# Freedom_Proto_v2.net
KiCad netlist of a schematic drawn in EAGLE
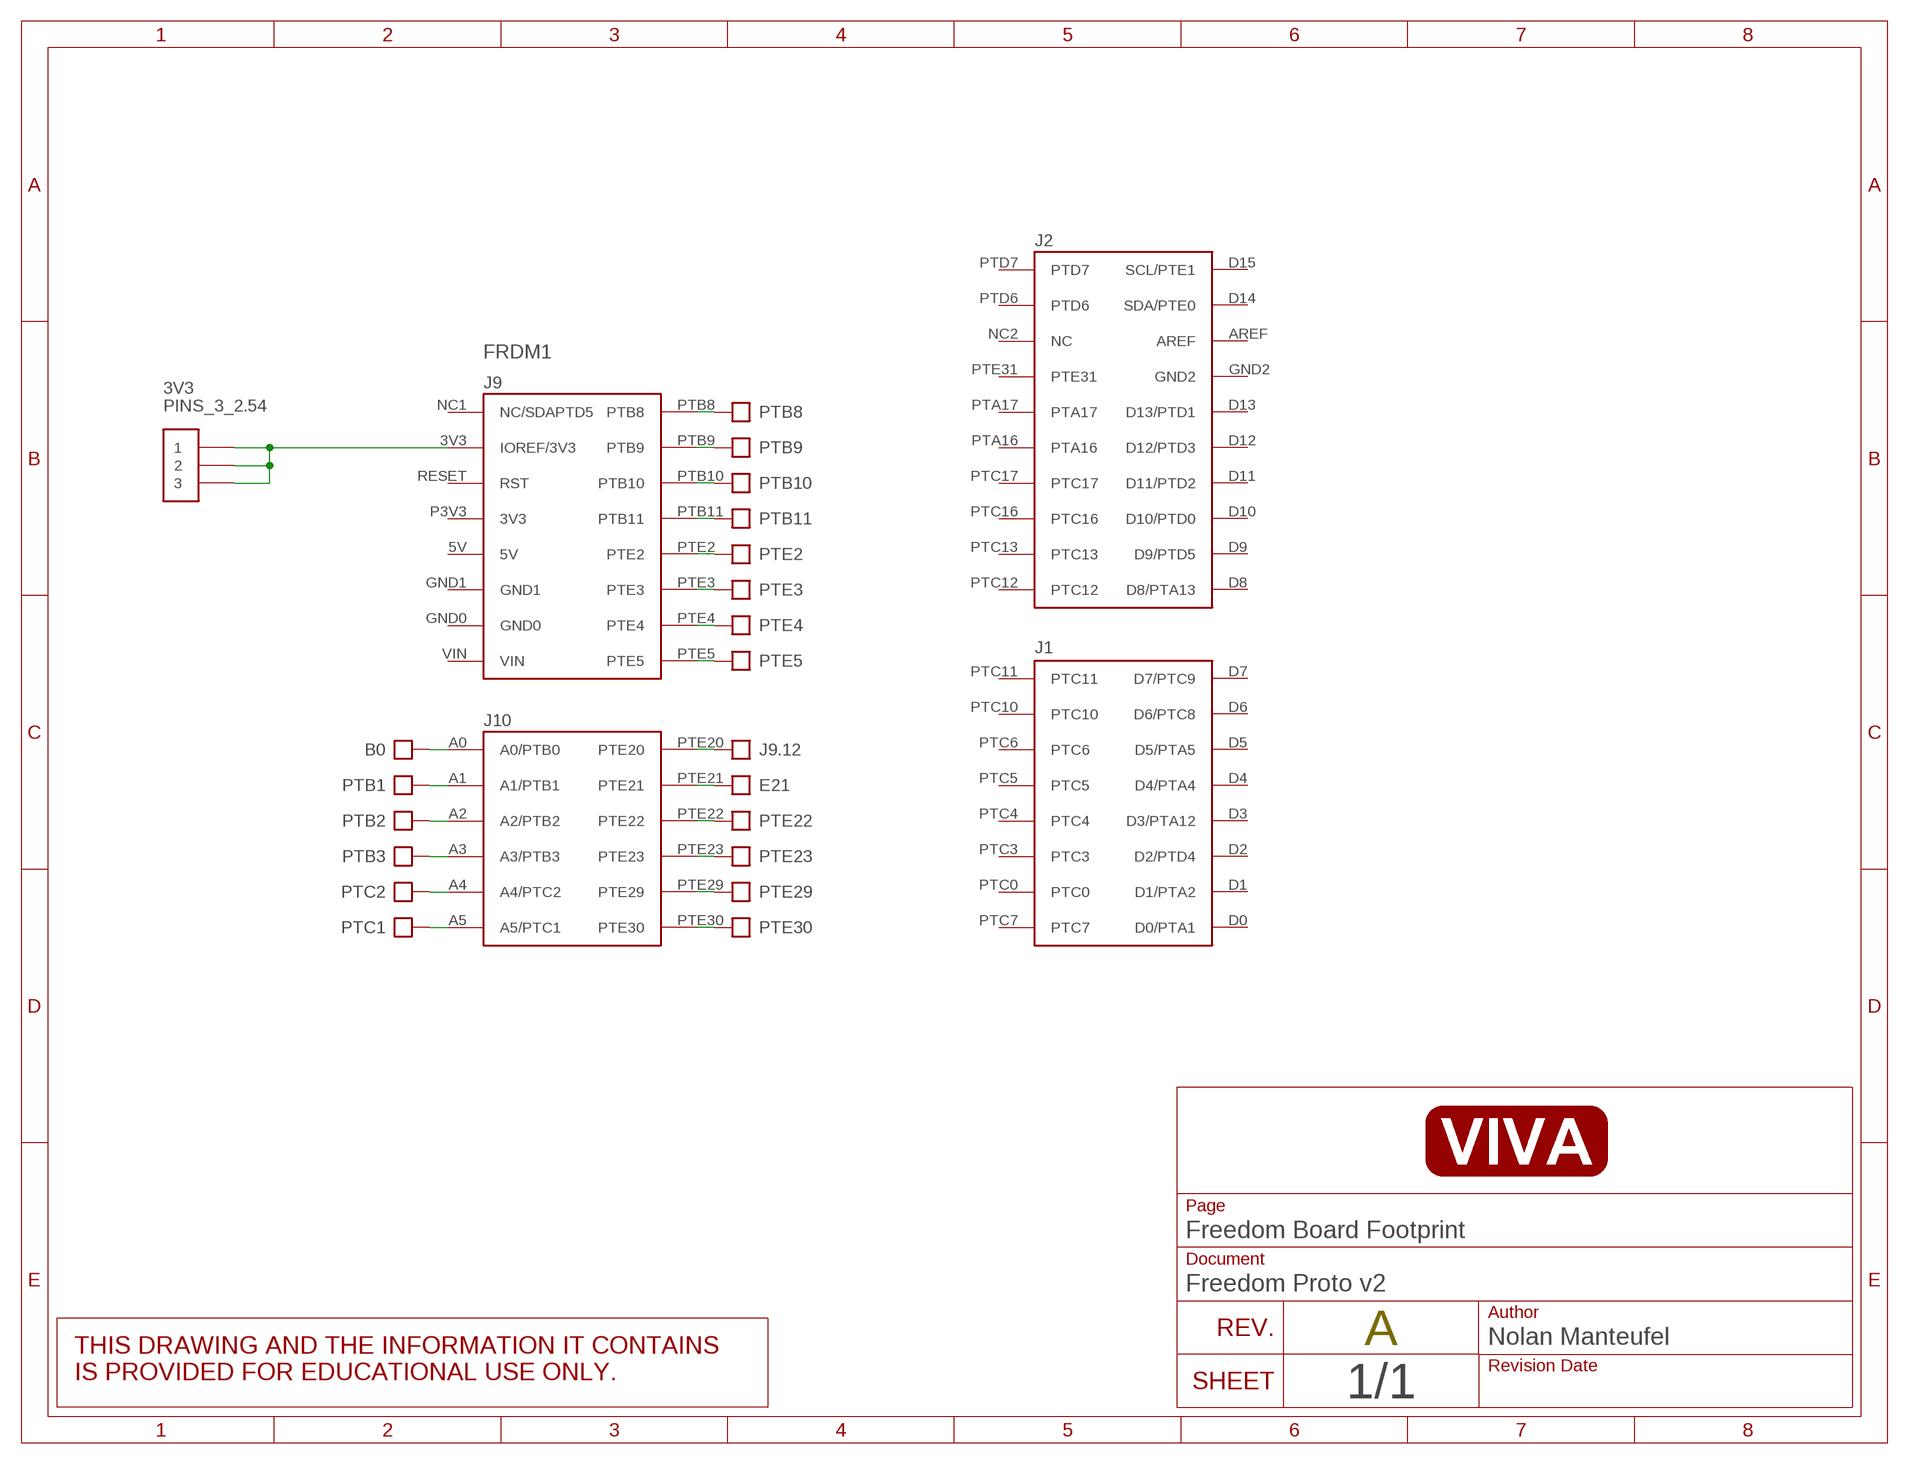
[diagram p0: schematic, sheet 1]

(export (version "E")
  (design (tool "Eeschema 10.0.6"))
  (components
    (comp (ref "3V3")
      (value "PINS_3_2.54")
      (footprint "eagle-import:PINS_3")
      (libsource (lib "eagle-import") (part "PINS_3_2.54"))
    )
    (comp (ref "B0")
      (value "PINS_1")
      (footprint "eagle-import:PINS_1_TEXT")
      (libsource (lib "eagle-import") (part "PINS_1"))
    )
    (comp (ref "E21")
      (value "PINS_1")
      (footprint "eagle-import:PINS_1_TEXT")
      (libsource (lib "eagle-import") (part "PINS_1"))
    )
    (comp (ref "FRDM1")
      (value "FRDM-KL25ZNORMAL")
      (footprint "eagle-import:FRDM_KL25Z_NORMAL")
      (libsource (lib "eagle-import") (part "FRDM-KL25ZNORMAL"))
    )
    (comp (ref "J9.12")
      (value "PINS_1")
      (footprint "eagle-import:PINS_1_TEXT")
      (libsource (lib "eagle-import") (part "PINS_1"))
    )
    (comp (ref "PTB1")
      (value "PINS_1")
      (footprint "eagle-import:PINS_1_TEXT")
      (libsource (lib "eagle-import") (part "PINS_1"))
    )
    (comp (ref "PTB2")
      (value "PINS_1")
      (footprint "eagle-import:PINS_1_TEXT")
      (libsource (lib "eagle-import") (part "PINS_1"))
    )
    (comp (ref "PTB3")
      (value "PINS_1")
      (footprint "eagle-import:PINS_1_TEXT")
      (libsource (lib "eagle-import") (part "PINS_1"))
    )
    (comp (ref "PTB8")
      (value "PINS_1")
      (footprint "eagle-import:PINS_1_TEXT")
      (libsource (lib "eagle-import") (part "PINS_1"))
    )
    (comp (ref "PTB9")
      (value "PINS_1")
      (footprint "eagle-import:PINS_1_TEXT")
      (libsource (lib "eagle-import") (part "PINS_1"))
    )
    (comp (ref "PTB10")
      (value "PINS_1")
      (footprint "eagle-import:PINS_1_TEXT")
      (libsource (lib "eagle-import") (part "PINS_1"))
    )
    (comp (ref "PTB11")
      (value "PINS_1")
      (footprint "eagle-import:PINS_1_TEXT")
      (libsource (lib "eagle-import") (part "PINS_1"))
    )
    (comp (ref "PTC1")
      (value "PINS_1")
      (footprint "eagle-import:PINS_1_TEXT")
      (libsource (lib "eagle-import") (part "PINS_1"))
    )
    (comp (ref "PTC2")
      (value "PINS_1")
      (footprint "eagle-import:PINS_1_TEXT")
      (libsource (lib "eagle-import") (part "PINS_1"))
    )
    (comp (ref "PTE2")
      (value "PINS_1")
      (footprint "eagle-import:PINS_1_TEXT")
      (libsource (lib "eagle-import") (part "PINS_1"))
    )
    (comp (ref "PTE3")
      (value "PINS_1")
      (footprint "eagle-import:PINS_1_TEXT")
      (libsource (lib "eagle-import") (part "PINS_1"))
    )
    (comp (ref "PTE4")
      (value "PINS_1")
      (footprint "eagle-import:PINS_1_TEXT")
      (libsource (lib "eagle-import") (part "PINS_1"))
    )
    (comp (ref "PTE5")
      (value "PINS_1")
      (footprint "eagle-import:PINS_1_TEXT")
      (libsource (lib "eagle-import") (part "PINS_1"))
    )
    (comp (ref "PTE22")
      (value "PINS_1")
      (footprint "eagle-import:PINS_1_TEXT")
      (libsource (lib "eagle-import") (part "PINS_1"))
    )
    (comp (ref "PTE23")
      (value "PINS_1")
      (footprint "eagle-import:PINS_1_TEXT")
      (libsource (lib "eagle-import") (part "PINS_1"))
    )
    (comp (ref "PTE29")
      (value "PINS_1")
      (footprint "eagle-import:PINS_1_TEXT")
      (libsource (lib "eagle-import") (part "PINS_1"))
    )
    (comp (ref "PTE30")
      (value "PINS_1")
      (footprint "eagle-import:PINS_1_TEXT")
      (libsource (lib "eagle-import") (part "PINS_1"))
    )
  )
  (nets
    (net (code "1") (name "Net-(E21-Pad1)") (class "Default")
      (node (ref "E21") (pin "1") (pinfunction "1_1") (pintype "bidirectional"))
      (node (ref "FRDM1") (pin "PTE21") (pinfunction "PTE21_PTE21") (pintype "bidirectional"))
    )
    (net (code "2") (name "Net-(FRDM1-A0{slash}PTB0)") (class "Default")
      (node (ref "B0") (pin "1") (pinfunction "1_1") (pintype "bidirectional"))
      (node (ref "FRDM1") (pin "A0") (pinfunction "A0/PTB0_A0") (pintype "bidirectional"))
    )
    (net (code "3") (name "Net-(FRDM1-A1{slash}PTB1)") (class "Default")
      (node (ref "FRDM1") (pin "A1") (pinfunction "A1/PTB1_A1") (pintype "bidirectional"))
      (node (ref "PTB1") (pin "1") (pinfunction "1_1") (pintype "bidirectional"))
    )
    (net (code "4") (name "Net-(FRDM1-A2{slash}PTB2)") (class "Default")
      (node (ref "FRDM1") (pin "A2") (pinfunction "A2/PTB2_A2") (pintype "bidirectional"))
      (node (ref "PTB2") (pin "1") (pinfunction "1_1") (pintype "bidirectional"))
    )
    (net (code "5") (name "Net-(FRDM1-A3{slash}PTB3)") (class "Default")
      (node (ref "FRDM1") (pin "A3") (pinfunction "A3/PTB3_A3") (pintype "bidirectional"))
      (node (ref "PTB3") (pin "1") (pinfunction "1_1") (pintype "bidirectional"))
    )
    (net (code "6") (name "Net-(FRDM1-A4{slash}PTC2)") (class "Default")
      (node (ref "FRDM1") (pin "A4") (pinfunction "A4/PTC2_A4") (pintype "bidirectional"))
      (node (ref "PTC2") (pin "1") (pinfunction "1_1") (pintype "bidirectional"))
    )
    (net (code "7") (name "Net-(FRDM1-A5{slash}PTC1)") (class "Default")
      (node (ref "FRDM1") (pin "A5") (pinfunction "A5/PTC1_A5") (pintype "bidirectional"))
      (node (ref "PTC1") (pin "1") (pinfunction "1_1") (pintype "bidirectional"))
    )
    (net (code "8") (name "Net-(FRDM1-IOREF{slash}3V3)") (class "Default")
      (node (ref "3V3") (pin "1") (pinfunction "1_1") (pintype "bidirectional"))
      (node (ref "3V3") (pin "2") (pinfunction "2_2") (pintype "bidirectional"))
      (node (ref "3V3") (pin "3") (pinfunction "3_3") (pintype "bidirectional"))
      (node (ref "FRDM1") (pin "3V3") (pinfunction "IOREF/3V3_3V3") (pintype "bidirectional"))
    )
    (net (code "9") (name "Net-(FRDM1-PadPTB8)") (class "Default")
      (node (ref "FRDM1") (pin "PTB8") (pinfunction "PTB8_PTB8") (pintype "bidirectional"))
      (node (ref "PTB8") (pin "1") (pinfunction "1_1") (pintype "bidirectional"))
    )
    (net (code "10") (name "Net-(FRDM1-PadPTB9)") (class "Default")
      (node (ref "FRDM1") (pin "PTB9") (pinfunction "PTB9_PTB9") (pintype "bidirectional"))
      (node (ref "PTB9") (pin "1") (pinfunction "1_1") (pintype "bidirectional"))
    )
    (net (code "11") (name "Net-(FRDM1-PadPTB10)") (class "Default")
      (node (ref "FRDM1") (pin "PTB10") (pinfunction "PTB10_PTB10") (pintype "bidirectional"))
      (node (ref "PTB10") (pin "1") (pinfunction "1_1") (pintype "bidirectional"))
    )
    (net (code "12") (name "Net-(FRDM1-PadPTB11)") (class "Default")
      (node (ref "FRDM1") (pin "PTB11") (pinfunction "PTB11_PTB11") (pintype "bidirectional"))
      (node (ref "PTB11") (pin "1") (pinfunction "1_1") (pintype "bidirectional"))
    )
    (net (code "13") (name "Net-(FRDM1-PadPTE2)") (class "Default")
      (node (ref "FRDM1") (pin "PTE2") (pinfunction "PTE2_PTE2") (pintype "bidirectional"))
      (node (ref "PTE2") (pin "1") (pinfunction "1_1") (pintype "bidirectional"))
    )
    (net (code "14") (name "Net-(FRDM1-PadPTE3)") (class "Default")
      (node (ref "FRDM1") (pin "PTE3") (pinfunction "PTE3_PTE3") (pintype "bidirectional"))
      (node (ref "PTE3") (pin "1") (pinfunction "1_1") (pintype "bidirectional"))
    )
    (net (code "15") (name "Net-(FRDM1-PadPTE4)") (class "Default")
      (node (ref "FRDM1") (pin "PTE4") (pinfunction "PTE4_PTE4") (pintype "bidirectional"))
      (node (ref "PTE4") (pin "1") (pinfunction "1_1") (pintype "bidirectional"))
    )
    (net (code "16") (name "Net-(FRDM1-PadPTE5)") (class "Default")
      (node (ref "FRDM1") (pin "PTE5") (pinfunction "PTE5_PTE5") (pintype "bidirectional"))
      (node (ref "PTE5") (pin "1") (pinfunction "1_1") (pintype "bidirectional"))
    )
    (net (code "17") (name "Net-(FRDM1-PadPTE20)") (class "Default")
      (node (ref "FRDM1") (pin "PTE20") (pinfunction "PTE20_PTE20") (pintype "bidirectional"))
      (node (ref "J9.12") (pin "1") (pinfunction "1_1") (pintype "bidirectional"))
    )
    (net (code "18") (name "Net-(FRDM1-PadPTE22)") (class "Default")
      (node (ref "FRDM1") (pin "PTE22") (pinfunction "PTE22_PTE22") (pintype "bidirectional"))
      (node (ref "PTE22") (pin "1") (pinfunction "1_1") (pintype "bidirectional"))
    )
    (net (code "19") (name "Net-(FRDM1-PadPTE23)") (class "Default")
      (node (ref "FRDM1") (pin "PTE23") (pinfunction "PTE23_PTE23") (pintype "bidirectional"))
      (node (ref "PTE23") (pin "1") (pinfunction "1_1") (pintype "bidirectional"))
    )
    (net (code "20") (name "Net-(FRDM1-PadPTE29)") (class "Default")
      (node (ref "FRDM1") (pin "PTE29") (pinfunction "PTE29_PTE29") (pintype "bidirectional"))
      (node (ref "PTE29") (pin "1") (pinfunction "1_1") (pintype "bidirectional"))
    )
    (net (code "21") (name "Net-(FRDM1-PadPTE30)") (class "Default")
      (node (ref "FRDM1") (pin "PTE30") (pinfunction "PTE30_PTE30") (pintype "bidirectional"))
      (node (ref "PTE30") (pin "1") (pinfunction "1_1") (pintype "bidirectional"))
    )
    (net (code "22") (name "unconnected-(FRDM1-3V3-PadP3V3)") (class "Default")
      (node (ref "FRDM1") (pin "P3V3") (pinfunction "3V3_P3V3") (pintype "bidirectional"))
    )
    (net (code "23") (name "unconnected-(FRDM1-D0{slash}PTA1-PadD0)") (class "Default")
      (node (ref "FRDM1") (pin "D0") (pinfunction "D0/PTA1_D0") (pintype "bidirectional"))
    )
    (net (code "24") (name "unconnected-(FRDM1-D1{slash}PTA2-PadD1)") (class "Default")
      (node (ref "FRDM1") (pin "D1") (pinfunction "D1/PTA2_D1") (pintype "bidirectional"))
    )
    (net (code "25") (name "unconnected-(FRDM1-D2{slash}PTD4-PadD2)") (class "Default")
      (node (ref "FRDM1") (pin "D2") (pinfunction "D2/PTD4_D2") (pintype "bidirectional"))
    )
    (net (code "26") (name "unconnected-(FRDM1-D3{slash}PTA12-PadD3)") (class "Default")
      (node (ref "FRDM1") (pin "D3") (pinfunction "D3/PTA12_D3") (pintype "bidirectional"))
    )
    (net (code "27") (name "unconnected-(FRDM1-D4{slash}PTA4-PadD4)") (class "Default")
      (node (ref "FRDM1") (pin "D4") (pinfunction "D4/PTA4_D4") (pintype "bidirectional"))
    )
    (net (code "28") (name "unconnected-(FRDM1-D5{slash}PTA5-PadD5)") (class "Default")
      (node (ref "FRDM1") (pin "D5") (pinfunction "D5/PTA5_D5") (pintype "bidirectional"))
    )
    (net (code "29") (name "unconnected-(FRDM1-D6{slash}PTC8-PadD6)") (class "Default")
      (node (ref "FRDM1") (pin "D6") (pinfunction "D6/PTC8_D6") (pintype "bidirectional"))
    )
    (net (code "30") (name "unconnected-(FRDM1-D7{slash}PTC9-PadD7)") (class "Default")
      (node (ref "FRDM1") (pin "D7") (pinfunction "D7/PTC9_D7") (pintype "bidirectional"))
    )
    (net (code "31") (name "unconnected-(FRDM1-D8{slash}PTA13-PadD8)") (class "Default")
      (node (ref "FRDM1") (pin "D8") (pinfunction "D8/PTA13_D8") (pintype "bidirectional"))
    )
    (net (code "32") (name "unconnected-(FRDM1-D9{slash}PTD5-PadD9)") (class "Default")
      (node (ref "FRDM1") (pin "D9") (pinfunction "D9/PTD5_D9") (pintype "bidirectional"))
    )
    (net (code "33") (name "unconnected-(FRDM1-D10{slash}PTD0-PadD10)") (class "Default")
      (node (ref "FRDM1") (pin "D10") (pinfunction "D10/PTD0_D10") (pintype "bidirectional"))
    )
    (net (code "34") (name "unconnected-(FRDM1-D11{slash}PTD2-PadD11)") (class "Default")
      (node (ref "FRDM1") (pin "D11") (pinfunction "D11/PTD2_D11") (pintype "bidirectional"))
    )
    (net (code "35") (name "unconnected-(FRDM1-D12{slash}PTD3-PadD12)") (class "Default")
      (node (ref "FRDM1") (pin "D12") (pinfunction "D12/PTD3_D12") (pintype "bidirectional"))
    )
    (net (code "36") (name "unconnected-(FRDM1-D13{slash}PTD1-PadD13)") (class "Default")
      (node (ref "FRDM1") (pin "D13") (pinfunction "D13/PTD1_D13") (pintype "bidirectional"))
    )
    (net (code "37") (name "unconnected-(FRDM1-NC-PadNC2)") (class "Default")
      (node (ref "FRDM1") (pin "NC2") (pinfunction "NC_NC2") (pintype "bidirectional"))
    )
    (net (code "38") (name "unconnected-(FRDM1-NC{slash}SDAPTD5-PadNC1)") (class "Default")
      (node (ref "FRDM1") (pin "NC1") (pinfunction "NC/SDAPTD5_NC1") (pintype "bidirectional"))
    )
    (net (code "39") (name "unconnected-(FRDM1-Pad5V)") (class "Default")
      (node (ref "FRDM1") (pin "5V") (pinfunction "5V_5V") (pintype "bidirectional"))
    )
    (net (code "40") (name "unconnected-(FRDM1-PadAREF)") (class "Default")
      (node (ref "FRDM1") (pin "AREF") (pinfunction "AREF_AREF") (pintype "bidirectional"))
    )
    (net (code "41") (name "unconnected-(FRDM1-PadGND0)") (class "Default")
      (node (ref "FRDM1") (pin "GND0") (pinfunction "GND0_GND0") (pintype "bidirectional"))
    )
    (net (code "42") (name "unconnected-(FRDM1-PadGND1)") (class "Default")
      (node (ref "FRDM1") (pin "GND1") (pinfunction "GND1_GND1") (pintype "bidirectional"))
    )
    (net (code "43") (name "unconnected-(FRDM1-PadGND2)") (class "Default")
      (node (ref "FRDM1") (pin "GND2") (pinfunction "GND2_GND2") (pintype "bidirectional"))
    )
    (net (code "44") (name "unconnected-(FRDM1-PadPTA16)") (class "Default")
      (node (ref "FRDM1") (pin "PTA16") (pinfunction "PTA16_PTA16") (pintype "bidirectional"))
    )
    (net (code "45") (name "unconnected-(FRDM1-PadPTA17)") (class "Default")
      (node (ref "FRDM1") (pin "PTA17") (pinfunction "PTA17_PTA17") (pintype "bidirectional"))
    )
    (net (code "46") (name "unconnected-(FRDM1-PadPTC0)") (class "Default")
      (node (ref "FRDM1") (pin "PTC0") (pinfunction "PTC0_PTC0") (pintype "bidirectional"))
    )
    (net (code "47") (name "unconnected-(FRDM1-PadPTC3)") (class "Default")
      (node (ref "FRDM1") (pin "PTC3") (pinfunction "PTC3_PTC3") (pintype "bidirectional"))
    )
    (net (code "48") (name "unconnected-(FRDM1-PadPTC4)") (class "Default")
      (node (ref "FRDM1") (pin "PTC4") (pinfunction "PTC4_PTC4") (pintype "bidirectional"))
    )
    (net (code "49") (name "unconnected-(FRDM1-PadPTC5)") (class "Default")
      (node (ref "FRDM1") (pin "PTC5") (pinfunction "PTC5_PTC5") (pintype "bidirectional"))
    )
    (net (code "50") (name "unconnected-(FRDM1-PadPTC6)") (class "Default")
      (node (ref "FRDM1") (pin "PTC6") (pinfunction "PTC6_PTC6") (pintype "bidirectional"))
    )
    (net (code "51") (name "unconnected-(FRDM1-PadPTC7)") (class "Default")
      (node (ref "FRDM1") (pin "PTC7") (pinfunction "PTC7_PTC7") (pintype "bidirectional"))
    )
    (net (code "52") (name "unconnected-(FRDM1-PadPTC10)") (class "Default")
      (node (ref "FRDM1") (pin "PTC10") (pinfunction "PTC10_PTC10") (pintype "bidirectional"))
    )
    (net (code "53") (name "unconnected-(FRDM1-PadPTC11)") (class "Default")
      (node (ref "FRDM1") (pin "PTC11") (pinfunction "PTC11_PTC11") (pintype "bidirectional"))
    )
    (net (code "54") (name "unconnected-(FRDM1-PadPTC12)") (class "Default")
      (node (ref "FRDM1") (pin "PTC12") (pinfunction "PTC12_PTC12") (pintype "bidirectional"))
    )
    (net (code "55") (name "unconnected-(FRDM1-PadPTC13)") (class "Default")
      (node (ref "FRDM1") (pin "PTC13") (pinfunction "PTC13_PTC13") (pintype "bidirectional"))
    )
    (net (code "56") (name "unconnected-(FRDM1-PadPTC16)") (class "Default")
      (node (ref "FRDM1") (pin "PTC16") (pinfunction "PTC16_PTC16") (pintype "bidirectional"))
    )
    (net (code "57") (name "unconnected-(FRDM1-PadPTC17)") (class "Default")
      (node (ref "FRDM1") (pin "PTC17") (pinfunction "PTC17_PTC17") (pintype "bidirectional"))
    )
    (net (code "58") (name "unconnected-(FRDM1-PadPTD6)") (class "Default")
      (node (ref "FRDM1") (pin "PTD6") (pinfunction "PTD6_PTD6") (pintype "bidirectional"))
    )
    (net (code "59") (name "unconnected-(FRDM1-PadPTD7)") (class "Default")
      (node (ref "FRDM1") (pin "PTD7") (pinfunction "PTD7_PTD7") (pintype "bidirectional"))
    )
    (net (code "60") (name "unconnected-(FRDM1-PadPTE31)") (class "Default")
      (node (ref "FRDM1") (pin "PTE31") (pinfunction "PTE31_PTE31") (pintype "bidirectional"))
    )
    (net (code "61") (name "unconnected-(FRDM1-PadVIN)") (class "Default")
      (node (ref "FRDM1") (pin "VIN") (pinfunction "VIN_VIN") (pintype "bidirectional"))
    )
    (net (code "62") (name "unconnected-(FRDM1-RST-PadRESET)") (class "Default")
      (node (ref "FRDM1") (pin "RESET") (pinfunction "RST_RESET") (pintype "bidirectional"))
    )
    (net (code "63") (name "unconnected-(FRDM1-SCL{slash}PTE1-PadD15)") (class "Default")
      (node (ref "FRDM1") (pin "D15") (pinfunction "SCL/PTE1_D15") (pintype "bidirectional"))
    )
    (net (code "64") (name "unconnected-(FRDM1-SDA{slash}PTE0-PadD14)") (class "Default")
      (node (ref "FRDM1") (pin "D14") (pinfunction "SDA/PTE0_D14") (pintype "bidirectional"))
    )
  )
)
